# dozimetr.net
KiCad netlist of a schematic drawn in EAGLE
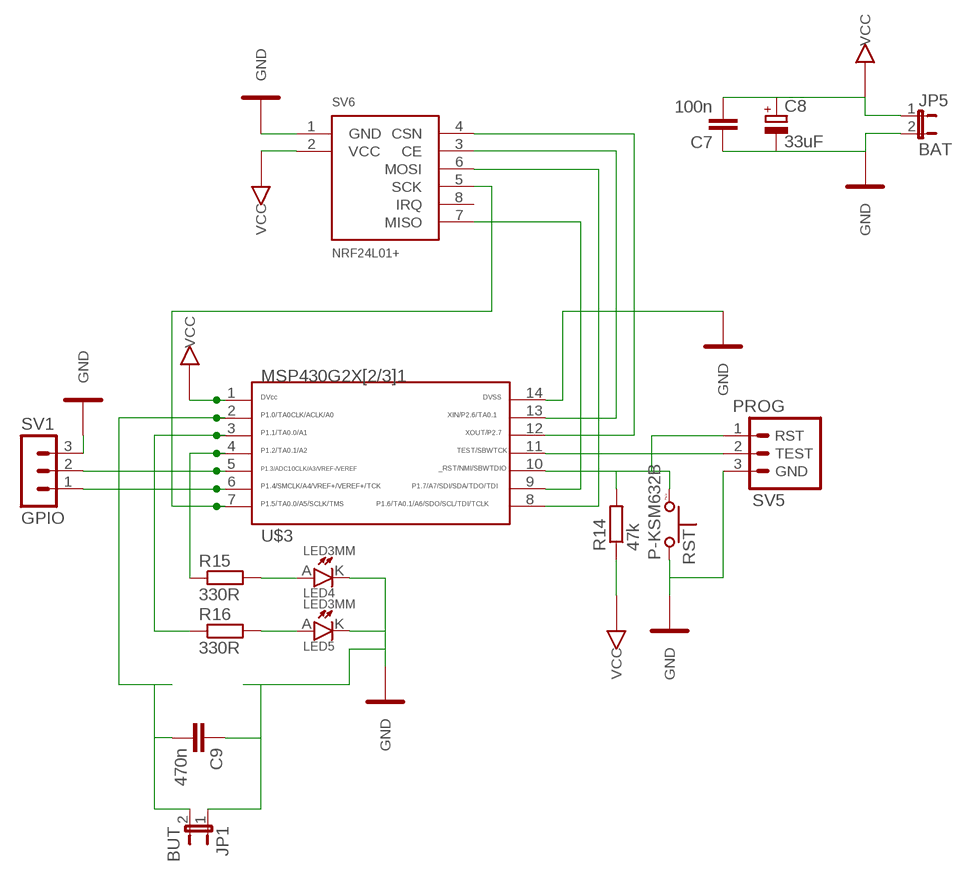
[diagram p0: schematic, sheet 1]

(export (version "E")
  (design (tool "Eeschema 10.0.6"))
  (components
    (comp (ref "C7")
      (value "100n")
      (footprint "eagle-import:C0805")
      (libsource (lib "eagle-import") (part "C-EUC0805"))
    )
    (comp (ref "C8")
      (value "33uF")
      (footprint "eagle-import:E2,5-6E")
      (libsource (lib "eagle-import") (part "CPOL-EUE2,5-6E"))
    )
    (comp (ref "C9")
      (value "470n")
      (footprint "eagle-import:C0805K")
      (libsource (lib "eagle-import") (part "C-EUC0805K"))
    )
    (comp (ref "JP1")
      (value "BUT")
      (footprint "eagle-import:JP1")
      (libsource (lib "eagle-import") (part "JP1E"))
    )
    (comp (ref "JP5")
      (value "BAT")
      (footprint "eagle-import:JP1")
      (libsource (lib "eagle-import") (part "JP1E"))
    )
    (comp (ref "LED4")
      (value "LED3MM")
      (footprint "eagle-import:LED3MM")
      (libsource (lib "eagle-import") (part "LED3MM"))
    )
    (comp (ref "LED5")
      (value "LED3MM")
      (footprint "eagle-import:LED3MM")
      (libsource (lib "eagle-import") (part "LED3MM"))
    )
    (comp (ref "R14")
      (value "47k")
      (footprint "eagle-import:R0805")
      (libsource (lib "eagle-import") (part "R-EU_R0805"))
    )
    (comp (ref "R15")
      (value "330R")
      (footprint "eagle-import:R0805")
      (libsource (lib "eagle-import") (part "R-EU_R0805"))
    )
    (comp (ref "R16")
      (value "330R")
      (footprint "eagle-import:R0805")
      (libsource (lib "eagle-import") (part "R-EU_R0805"))
    )
    (comp (ref "RST")
      (value "P-KSM632B")
      (footprint "eagle-import:P-KSM632B")
      (libsource (lib "eagle-import") (part "P-KSM632B"))
    )
    (comp (ref "SV1")
      (value "GPIO")
      (footprint "eagle-import:MA03-1")
      (libsource (lib "eagle-import") (part "con-lstb_MA03-1"))
    )
    (comp (ref "SV5")
      (value "PROG")
      (footprint "eagle-import:MA03-1")
      (libsource (lib "eagle-import") (part "MA03-1"))
    )
    (comp (ref "SV6")
      (value "NRF24L01+")
      (footprint "eagle-import:NRF24L01_MOD")
      (libsource (lib "eagle-import") (part "NRF24L01_MOD"))
    )
    (comp (ref "U$3")
      (value "G2X[2/3]1---PW14")
      (footprint "eagle-import:PW14")
      (libsource (lib "eagle-import") (part "G2X[2/3]1---PW14"))
    )
  )
  (nets
    (net (code "1") (name "GND") (class "Default")
      (node (ref "C7") (pin "1") (pinfunction "1_1") (pintype "passive"))
      (node (ref "C8") (pin "-") (pinfunction "-_-") (pintype "passive"))
      (node (ref "C9") (pin "1") (pinfunction "1_1") (pintype "passive"))
      (node (ref "JP1") (pin "1") (pinfunction "1_1") (pintype "passive"))
      (node (ref "JP5") (pin "2") (pinfunction "2_2") (pintype "passive"))
      (node (ref "LED4") (pin "K") (pinfunction "C_K") (pintype "bidirectional"))
      (node (ref "LED5") (pin "K") (pinfunction "C_K") (pintype "bidirectional"))
      (node (ref "RST") (pin "2") (pinfunction "2_2") (pintype "passive"))
      (node (ref "SV1") (pin "3") (pinfunction "3_3") (pintype "passive"))
      (node (ref "SV5") (pin "3") (pinfunction "GND_3") (pintype "passive"))
      (node (ref "SV6") (pin "1") (pinfunction "GND_1") (pintype "bidirectional"))
      (node (ref "U$3") (pin "14") (pinfunction "14_14") (pintype "bidirectional"))
    )
    (net (code "2") (name "Net-(C9-Pad2)") (class "Default")
      (node (ref "C9") (pin "2") (pinfunction "2_2") (pintype "passive"))
      (node (ref "JP1") (pin "2") (pinfunction "2_2") (pintype "passive"))
      (node (ref "U$3") (pin "2") (pinfunction "2_2") (pintype "bidirectional"))
    )
    (net (code "3") (name "Net-(LED4-PadA)") (class "Default")
      (node (ref "LED4") (pin "A") (pinfunction "A_A") (pintype "bidirectional"))
      (node (ref "R15") (pin "2") (pinfunction "2_2") (pintype "passive"))
    )
    (net (code "4") (name "Net-(LED5-PadA)") (class "Default")
      (node (ref "LED5") (pin "A") (pinfunction "A_A") (pintype "bidirectional"))
      (node (ref "R16") (pin "2") (pinfunction "2_2") (pintype "passive"))
    )
    (net (code "5") (name "Net-(R15-Pad1)") (class "Default")
      (node (ref "R15") (pin "1") (pinfunction "1_1") (pintype "passive"))
      (node (ref "U$3") (pin "4") (pinfunction "4_4") (pintype "bidirectional"))
    )
    (net (code "6") (name "Net-(R16-Pad1)") (class "Default")
      (node (ref "R16") (pin "1") (pinfunction "1_1") (pintype "passive"))
      (node (ref "U$3") (pin "3") (pinfunction "3_3") (pintype "bidirectional"))
    )
    (net (code "7") (name "Net-(SV1-Pad1)") (class "Default")
      (node (ref "SV1") (pin "1") (pinfunction "1_1") (pintype "passive"))
      (node (ref "U$3") (pin "6") (pinfunction "6_6") (pintype "bidirectional"))
    )
    (net (code "8") (name "Net-(SV1-Pad2)") (class "Default")
      (node (ref "SV1") (pin "2") (pinfunction "2_2") (pintype "passive"))
      (node (ref "U$3") (pin "5") (pinfunction "5_5") (pintype "bidirectional"))
    )
    (net (code "9") (name "Net-(SV5-RST)") (class "Default")
      (node (ref "R14") (pin "2") (pinfunction "2_2") (pintype "passive"))
      (node (ref "RST") (pin "1") (pinfunction "1_1") (pintype "passive"))
      (node (ref "SV5") (pin "1") (pinfunction "RST_1") (pintype "passive"))
      (node (ref "U$3") (pin "10") (pinfunction "10_10") (pintype "bidirectional"))
    )
    (net (code "10") (name "Net-(SV5-TEST)") (class "Default")
      (node (ref "SV5") (pin "2") (pinfunction "TEST_2") (pintype "passive"))
      (node (ref "U$3") (pin "11") (pinfunction "11_11") (pintype "bidirectional"))
    )
    (net (code "11") (name "Net-(SV6-CE)") (class "Default")
      (node (ref "SV6") (pin "3") (pinfunction "CE_3") (pintype "bidirectional"))
      (node (ref "U$3") (pin "13") (pinfunction "13_13") (pintype "bidirectional"))
    )
    (net (code "12") (name "Net-(SV6-CSN)") (class "Default")
      (node (ref "SV6") (pin "4") (pinfunction "CSN_4") (pintype "bidirectional"))
      (node (ref "U$3") (pin "12") (pinfunction "12_12") (pintype "bidirectional"))
    )
    (net (code "13") (name "Net-(SV6-MISO)") (class "Default")
      (node (ref "SV6") (pin "7") (pinfunction "MISO_7") (pintype "bidirectional"))
      (node (ref "U$3") (pin "9") (pinfunction "9_9") (pintype "bidirectional"))
    )
    (net (code "14") (name "Net-(SV6-MOSI)") (class "Default")
      (node (ref "SV6") (pin "6") (pinfunction "MOSI_6") (pintype "bidirectional"))
      (node (ref "U$3") (pin "8") (pinfunction "8_8") (pintype "bidirectional"))
    )
    (net (code "15") (name "Net-(SV6-SCK)") (class "Default")
      (node (ref "SV6") (pin "5") (pinfunction "SCK_5") (pintype "bidirectional"))
      (node (ref "U$3") (pin "7") (pinfunction "7_7") (pintype "bidirectional"))
    )
    (net (code "16") (name "VCC") (class "Default")
      (node (ref "C7") (pin "2") (pinfunction "2_2") (pintype "passive"))
      (node (ref "C8") (pin "+") (pinfunction "+_+") (pintype "passive"))
      (node (ref "JP5") (pin "1") (pinfunction "1_1") (pintype "passive"))
      (node (ref "R14") (pin "1") (pinfunction "1_1") (pintype "passive"))
      (node (ref "SV6") (pin "2") (pinfunction "VCC_2") (pintype "bidirectional"))
      (node (ref "U$3") (pin "1") (pinfunction "1_1") (pintype "bidirectional"))
    )
    (net (code "17") (name "unconnected-(SV6-IRQ-Pad8)") (class "Default")
      (node (ref "SV6") (pin "8") (pinfunction "IRQ_8") (pintype "bidirectional"))
    )
  )
)
